# ConstController.net
KiCad netlist of a schematic drawn in Altium Designer
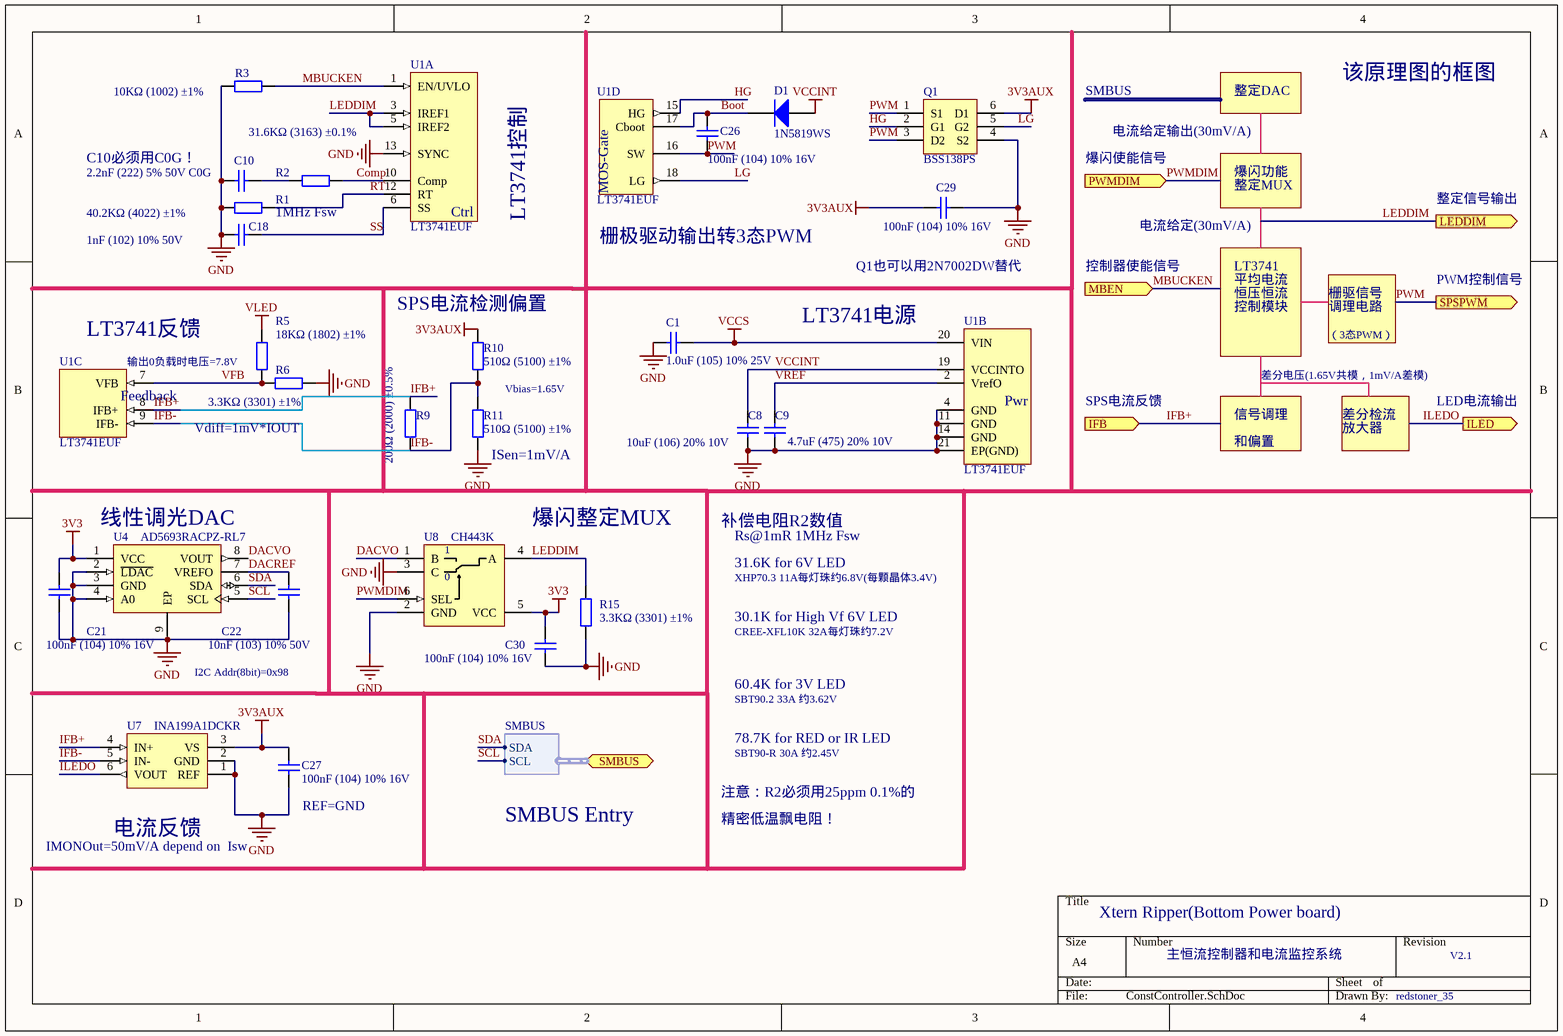
[diagram p0: ConstController.SchDoc]

(export (version "E")
  (design (tool "Eeschema 10.0.6"))
  (components
    (comp (ref "C1")
      (value "1.0uF (105) 10% 25V")
      (footprint "0402_C")
      (description "贴片电容")
      (libsource (lib "Miscellaneous Devices LC") (part "0402 1.0uF (105) 10% 25V"))
    )
    (comp (ref "C8")
      (value "10uF (106) 20% 10V")
      (footprint "0402_C")
      (description "贴片电容")
      (libsource (lib "Miscellaneous Devices LC") (part "0402 4.7uF (475) 20% 10V"))
    )
    (comp (ref "C9")
      (value "4.7uF (475) 20% 10V")
      (footprint "0402_C")
      (description "贴片电容")
      (libsource (lib "Miscellaneous Devices LC") (part "0402 4.7uF (475) 20% 10V"))
    )
    (comp (ref "C10")
      (value "2.2nF (222) 5% 50V C0G")
      (footprint "0402_C")
      (description "贴片电容")
      (libsource (lib "Miscellaneous Devices LC") (part "0402 2.2nF (222) 10% 50V"))
    )
    (comp (ref "C18")
      (value "1nF (102) 10% 50V")
      (footprint "0402_C")
      (description "贴片电容")
      (libsource (lib "Miscellaneous Devices LC") (part "0402 1nF (102) 10% 50V"))
    )
    (comp (ref "C21")
      (value "100nF (104) 10% 16V")
      (footprint "0402_C")
      (description "贴片电容")
      (libsource (lib "Miscellaneous Devices LC") (part "0402 100nF (104) 10% 16V"))
    )
    (comp (ref "C22")
      (value "10nF (103) 10% 50V")
      (footprint "0402_C")
      (description "贴片电容")
      (libsource (lib "Miscellaneous Devices LC") (part "0402 10nF (103) 10% 50V"))
    )
    (comp (ref "C26")
      (value "100nF (104) 10% 16V")
      (footprint "0402_C")
      (description "贴片电容")
      (libsource (lib "Miscellaneous Devices LC") (part "0402 100nF (104) 10% 16V"))
    )
    (comp (ref "C27")
      (value "100nF (104) 10% 16V")
      (footprint "0402_C")
      (description "贴片电容")
      (libsource (lib "Miscellaneous Devices LC") (part "0402 100nF (104) 10% 16V"))
    )
    (comp (ref "C29")
      (value "100nF (104) 10% 16V")
      (footprint "0402_C")
      (description "贴片电容")
      (libsource (lib "Miscellaneous Devices LC") (part "0402 100nF (104) 10% 16V"))
    )
    (comp (ref "C30")
      (value "100nF (104) 10% 16V")
      (footprint "0402_C")
      (description "贴片电容")
      (libsource (lib "Miscellaneous Devices LC") (part "0402 100nF (104) 10% 16V"))
    )
    (comp (ref "D1")
      (value "1N5819WS")
      (footprint "SOD-323")
      (description "二极管")
      (libsource (lib "Miscellaneous Devices LC") (part "SOD-323 1N4148WS T4"))
    )
    (comp (ref "Q1")
      (value "BSS138PS")
      (footprint "SC70-6")
      (description "Dual N-Channel MOSFET 60V320mA SOT-363")
      (libsource (lib "custom") (part "2N7002DW"))
    )
    (comp (ref "R1")
      (value "40.2KΩ (4022) ±1%")
      (footprint "0402_R")
      (description "贴片电阻")
      (libsource (lib "") (part "0402 49.9KΩ (4992) 1%_1"))
    )
    (comp (ref "R2")
      (value "31.6KΩ (3163) ±0.1%")
      (footprint "0402_R")
      (description "贴片电阻")
      (libsource (lib "Miscellaneous Devices LC") (part "0402 49.9KΩ (4992) 1%"))
    )
    (comp (ref "R3")
      (value "10KΩ (1002) ±1%")
      (footprint "0402_R")
      (description "贴片电阻")
      (libsource (lib "Miscellaneous Devices LC") (part "0402 10KΩ (1002) 1%"))
    )
    (comp (ref "R5")
      (value "18KΩ (1802) ±1%")
      (footprint "0402_R")
      (description "贴片电阻")
      (libsource (lib "Miscellaneous Devices LC") (part "0402 18KΩ (1802) 1%"))
    )
    (comp (ref "R6")
      (value "3.3KΩ (3301) ±1%")
      (footprint "0402_R")
      (description "贴片电阻")
      (libsource (lib "Miscellaneous Devices LC") (part "0402 3.3KΩ (3301) 1%"))
    )
    (comp (ref "R9")
      (value "200Ω (2000) ±0.5%")
      (footprint "0402_R")
      (description "贴片电阻")
      (libsource (lib "Miscellaneous Devices LC") (part "0402 200Ω (2000) 1%"))
    )
    (comp (ref "R10")
      (value "510Ω (5100) ±1%")
      (footprint "0402_R")
      (description "贴片电阻")
      (libsource (lib "Miscellaneous Devices LC") (part "0402 510Ω (5100) 1%"))
    )
    (comp (ref "R11")
      (value "510Ω (5100) ±1%")
      (footprint "0402_R")
      (description "贴片电阻")
      (libsource (lib "Miscellaneous Devices LC") (part "0402 510Ω (5100) 1%"))
    )
    (comp (ref "R15")
      (value "3.3KΩ (3301) ±1%")
      (footprint "0402_R")
      (description "贴片电阻")
      (libsource (lib "") (part "0402 3.3KΩ (3301) 1%_1"))
    )
    (comp (ref "U1")
      (value "LT3741EUF")
      (footprint "UF-05-08-1710A")
      (description "Constant Voltage/Current Sync Buck controller(external switch)")
      (libsource (lib "custom") (part "LT3741EUF"))
    )
    (comp (ref "U4")
      (value "AD5693RACPZ-RL7")
      (footprint "LFCSP-8-10")
      (description "16bit I2C Nano DAC with 2.5V internal Ref in 2x2mm SON")
      (libsource (lib "custom") (part "AD5693RACPZ-RL7"))
    )
    (comp (ref "U7")
      (value "INA199A1DCKR")
      (footprint "SC70-6")
      (description "50Khz 50V/V 26V Max High Side Current Op Amp.")
      (libsource (lib "custom") (part "INA199A2DCKR"))
    )
    (comp (ref "U8")
      (value "CH443K")
      (footprint "SC70-6")
      (description "Low-Voltage Analog Switch SPDT,1.8-5V Power")
      (libsource (lib "custom") (part "NC7SB3157P6X"))
    )
  )
  (nets
    (net (code "2") (name "/Boot") (class "Default")
      (node (ref "C26") (pin "2") (pinfunction "2_2") (pintype "passive"))
      (node (ref "D1") (pin "2") (pinfunction "K_2") (pintype "passive"))
      (node (ref "U1") (pin "17") (pinfunction "Cboot_17") (pintype "passive"))
    )
    (net (code "3") (name "/Comp") (class "Default")
      (node (ref "R2") (pin "1") (pinfunction "1_1") (pintype "passive"))
      (node (ref "U1") (pin "10") (pinfunction "Comp_10") (pintype "passive"))
    )
    (net (code "4") (name "/DACREF") (class "Default")
      (node (ref "C22") (pin "2") (pinfunction "2_2") (pintype "passive"))
      (node (ref "U4") (pin "7") (pinfunction "VREFO_7") (pintype "passive"))
    )
    (net (code "5") (name "/DACVO") (class "Default")
      (node (ref "U4") (pin "8") (pinfunction "VOUT_8") (pintype "output"))
      (node (ref "U8") (pin "1") (pinfunction "B_1") (pintype "passive"))
    )
    (net (code "6") (name "/HG") (class "Default")
      (node (ref "Q1") (pin "2") (pinfunction "G1_2") (pintype "passive"))
      (node (ref "U1") (pin "15") (pinfunction "HG_15") (pintype "output"))
    )
    (net (code "7") (name "/IFB+") (class "Default")
      (node (ref "R9") (pin "2") (pinfunction "2_2") (pintype "passive"))
      (node (ref "U1") (pin "8") (pinfunction "IFB+_8") (pintype "input"))
      (node (ref "U7") (pin "4") (pinfunction "IN+_4") (pintype "input"))
    )
    (net (code "8") (name "/IFB-") (class "Default")
      (node (ref "R10") (pin "2") (pinfunction "2_2") (pintype "passive"))
      (node (ref "R11") (pin "1") (pinfunction "1_1") (pintype "passive"))
      (node (ref "R9") (pin "1") (pinfunction "1_1") (pintype "passive"))
      (node (ref "U1") (pin "9") (pinfunction "IFB-_9") (pintype "input"))
      (node (ref "U7") (pin "5") (pinfunction "IN-_5") (pintype "input"))
    )
    (net (code "9") (name "/ILEDO") (class "Default")
      (node (ref "U7") (pin "6") (pinfunction "VOUT_6") (pintype "output"))
    )
    (net (code "10") (name "/LEDDIM") (class "Default")
      (node (ref "R15") (pin "2") (pinfunction "2_2") (pintype "passive"))
      (node (ref "U1") (pin "3") (pinfunction "IREF1_3") (pintype "input"))
      (node (ref "U1") (pin "5") (pinfunction "IREF2_5") (pintype "input"))
      (node (ref "U8") (pin "4") (pinfunction "A_4") (pintype "passive"))
    )
    (net (code "11") (name "/LG") (class "Default")
      (node (ref "Q1") (pin "5") (pinfunction "G2_5") (pintype "passive"))
      (node (ref "U1") (pin "18") (pinfunction "LG_18") (pintype "output"))
    )
    (net (code "12") (name "/MBUCKEN") (class "Default")
      (node (ref "R3") (pin "2") (pinfunction "2_2") (pintype "passive"))
      (node (ref "U1") (pin "1") (pinfunction "EN/UVLO_1") (pintype "input"))
    )
    (net (code "13") (name "/PWM") (class "Default")
      (node (ref "C26") (pin "1") (pinfunction "1_1") (pintype "passive"))
      (node (ref "Q1") (pin "1") (pinfunction "S1_1") (pintype "passive"))
      (node (ref "Q1") (pin "3") (pinfunction "D2_3") (pintype "passive"))
      (node (ref "U1") (pin "16") (pinfunction "SW_16") (pintype "passive"))
    )
    (net (code "14") (name "/PWMDIM") (class "Default")
      (node (ref "U8") (pin "6") (pinfunction "SEL_6") (pintype "input"))
    )
    (net (code "15") (name "/RT") (class "Default")
      (node (ref "R1") (pin "2") (pinfunction "2_2") (pintype "passive"))
      (node (ref "U1") (pin "12") (pinfunction "RT_12") (pintype "passive"))
    )
    (net (code "16") (name "/SCL") (class "Default")
      (node (ref "U4") (pin "5") (pinfunction "SCL_5") (pintype "input"))
    )
    (net (code "17") (name "/SDA") (class "Default")
      (node (ref "U4") (pin "6") (pinfunction "SDA_6") (pintype "bidirectional"))
    )
    (net (code "18") (name "/SS") (class "Default")
      (node (ref "C18") (pin "2") (pinfunction "2_2") (pintype "passive"))
      (node (ref "U1") (pin "6") (pinfunction "SS_6") (pintype "passive"))
    )
    (net (code "19") (name "/VFB") (class "Default")
      (node (ref "R5") (pin "1") (pinfunction "1_1") (pintype "passive"))
      (node (ref "R6") (pin "1") (pinfunction "1_1") (pintype "passive"))
      (node (ref "U1") (pin "7") (pinfunction "VFB_7") (pintype "input"))
    )
    (net (code "20") (name "/VREF") (class "Default")
      (node (ref "C9") (pin "2") (pinfunction "2_2") (pintype "passive"))
      (node (ref "U1") (pin "2") (pinfunction "VrefO_2") (pintype "power_in"))
    )
    (net (code "22") (name "3V3") (class "Default")
      (node (ref "C21") (pin "2") (pinfunction "2_2") (pintype "passive"))
      (node (ref "C30") (pin "2") (pinfunction "2_2") (pintype "passive"))
      (node (ref "U4") (pin "1") (pinfunction "VCC_1") (pintype "power_in"))
      (node (ref "U8") (pin "5") (pinfunction "VCC_5") (pintype "power_in"))
    )
    (net (code "23") (name "3V3AUX") (class "Default")
      (node (ref "C27") (pin "1") (pinfunction "1_1") (pintype "passive"))
      (node (ref "C29") (pin "1") (pinfunction "1_1") (pintype "passive"))
      (node (ref "Q1") (pin "6") (pinfunction "D1_6") (pintype "passive"))
      (node (ref "R10") (pin "1") (pinfunction "1_1") (pintype "passive"))
      (node (ref "U7") (pin "3") (pinfunction "VS_3") (pintype "passive"))
    )
    (net (code "24") (name "GND") (class "Default")
      (node (ref "C1") (pin "1") (pinfunction "1_1") (pintype "passive"))
      (node (ref "C10") (pin "2") (pinfunction "2_2") (pintype "passive"))
      (node (ref "C18") (pin "1") (pinfunction "1_1") (pintype "passive"))
      (node (ref "C21") (pin "1") (pinfunction "1_1") (pintype "passive"))
      (node (ref "C22") (pin "1") (pinfunction "1_1") (pintype "passive"))
      (node (ref "C27") (pin "2") (pinfunction "2_2") (pintype "passive"))
      (node (ref "C29") (pin "2") (pinfunction "2_2") (pintype "passive"))
      (node (ref "C30") (pin "1") (pinfunction "1_1") (pintype "passive"))
      (node (ref "C8") (pin "1") (pinfunction "1_1") (pintype "passive"))
      (node (ref "C9") (pin "1") (pinfunction "1_1") (pintype "passive"))
      (node (ref "Q1") (pin "4") (pinfunction "S2_4") (pintype "passive"))
      (node (ref "R1") (pin "1") (pinfunction "1_1") (pintype "passive"))
      (node (ref "R11") (pin "2") (pinfunction "2_2") (pintype "passive"))
      (node (ref "R15") (pin "1") (pinfunction "1_1") (pintype "passive"))
      (node (ref "R3") (pin "1") (pinfunction "1_1") (pintype "passive"))
      (node (ref "R6") (pin "2") (pinfunction "2_2") (pintype "passive"))
      (node (ref "U1") (pin "11") (pinfunction "GND_11") (pintype "power_in"))
      (node (ref "U1") (pin "13") (pinfunction "SYNC_13") (pintype "input"))
      (node (ref "U1") (pin "14") (pinfunction "GND_14") (pintype "power_in"))
      (node (ref "U1") (pin "21") (pinfunction "EP(GND)_21") (pintype "power_in"))
      (node (ref "U1") (pin "4") (pinfunction "GND_4") (pintype "power_in"))
      (node (ref "U4") (pin "2") (pinfunction "~{LDAC}_2") (pintype "input"))
      (node (ref "U4") (pin "3") (pinfunction "GND_3") (pintype "power_in"))
      (node (ref "U4") (pin "4") (pinfunction "A0_4") (pintype "input"))
      (node (ref "U4") (pin "9") (pinfunction "EP_9") (pintype "passive"))
      (node (ref "U7") (pin "1") (pinfunction "REF_1") (pintype "passive"))
      (node (ref "U7") (pin "2") (pinfunction "GND_2") (pintype "passive"))
      (node (ref "U8") (pin "2") (pinfunction "GND_2") (pintype "power_in"))
      (node (ref "U8") (pin "3") (pinfunction "C_3") (pintype "passive"))
    )
    (net (code "25") (name "Net-(C10-Pad1)") (class "Default")
      (node (ref "C10") (pin "1") (pinfunction "1_1") (pintype "passive"))
      (node (ref "R2") (pin "2") (pinfunction "2_2") (pintype "passive"))
    )
    (net (code "26") (name "VCCINT") (class "Default")
      (node (ref "C8") (pin "2") (pinfunction "2_2") (pintype "passive"))
      (node (ref "D1") (pin "1") (pinfunction "A_1") (pintype "passive"))
      (node (ref "U1") (pin "19") (pinfunction "VCCINTO_19") (pintype "power_in"))
    )
    (net (code "27") (name "VCCS") (class "Default")
      (node (ref "C1") (pin "2") (pinfunction "2_2") (pintype "passive"))
      (node (ref "U1") (pin "20") (pinfunction "VIN_20") (pintype "power_in"))
    )
    (net (code "28") (name "VLED") (class "Default")
      (node (ref "R5") (pin "2") (pinfunction "2_2") (pintype "passive"))
    )
  )
)
